# MCU.net
KiCad netlist of a schematic drawn in Altium Designer
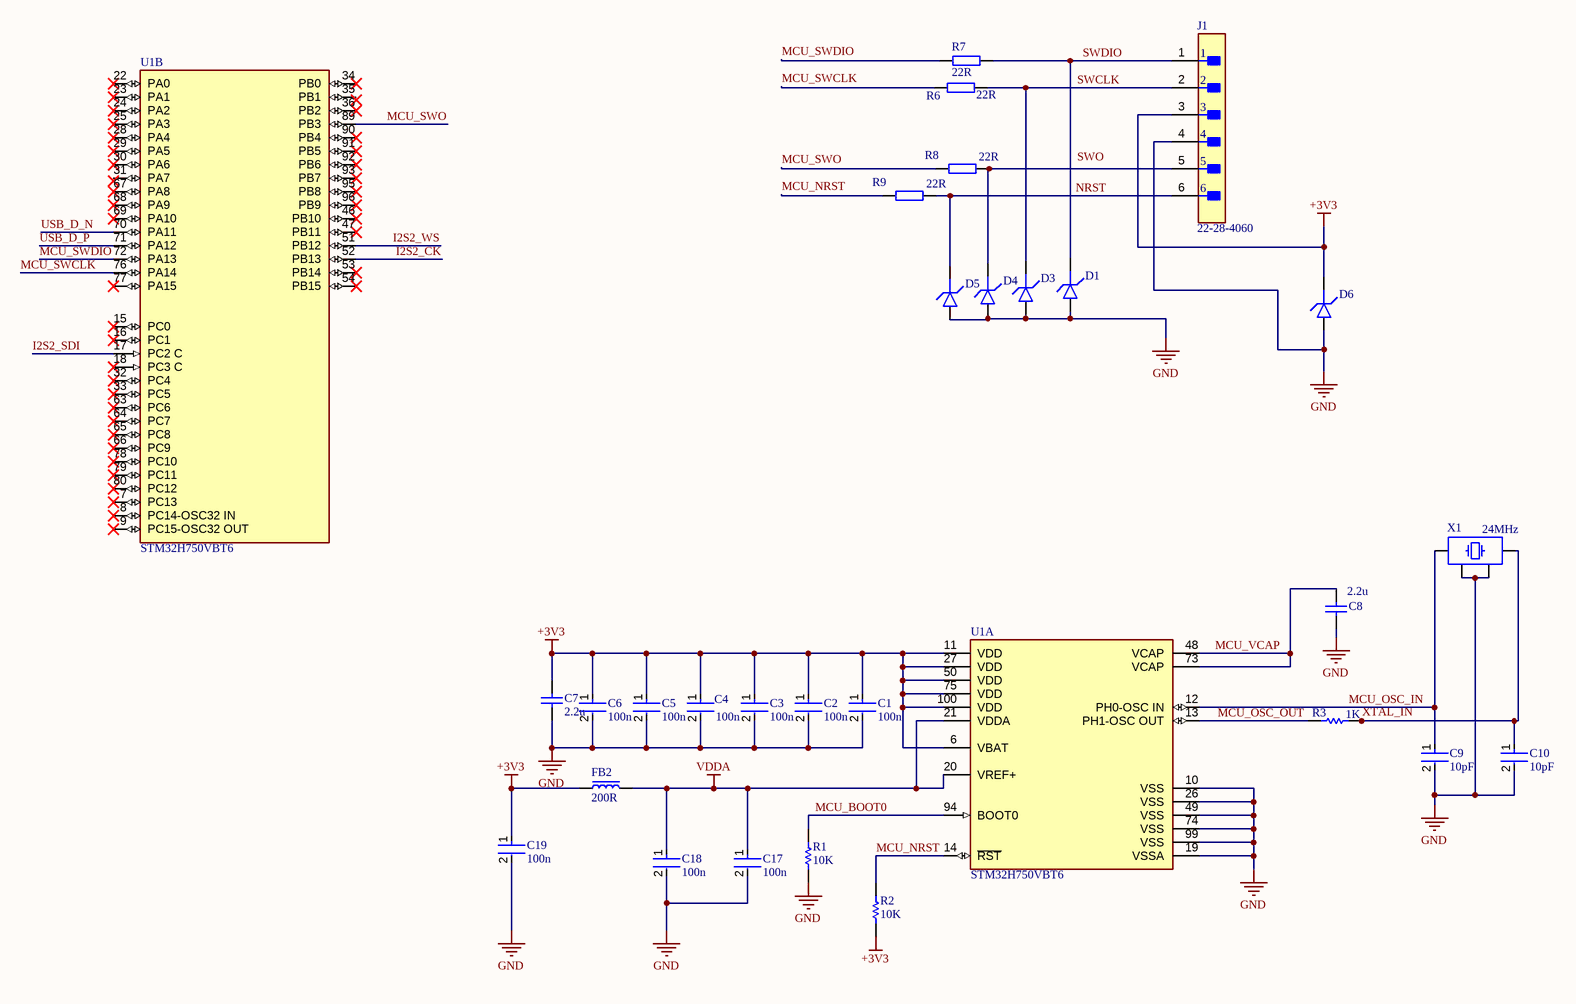
[diagram p0: MCU.SchDoc]

(export (version "E")
  (design (tool "Eeschema 10.0.6"))
  (components
    (comp (ref "C1")
      (value "100n")
      (footprint "FP-C0402-BB-MFG")
      (description "C0402 0.10 μF X7R 5.00% 16 V")
      (fields
        (field (name "OCTOPART") "https://octopart.com/c0402c104j4rac-kemet-24931384")
        (field (name "MANUFACTURER") "Kemet")
      )
      (libsource (lib "Altium Content Vault") (part "b4654b650e69147ec39a6b967a45e02"))
    )
    (comp (ref "C2")
      (value "100n")
      (footprint "FP-C0402-BB-MFG")
      (description "C0402 0.10 μF X7R 5.00% 16 V")
      (fields
        (field (name "OCTOPART") "https://octopart.com/c0402c104j4rac-kemet-24931384")
        (field (name "MANUFACTURER") "Kemet")
      )
      (libsource (lib "Altium Content Vault") (part "b4654b650e69147ec39a6b967a45e02"))
    )
    (comp (ref "C3")
      (value "100n")
      (footprint "FP-C0402-BB-MFG")
      (description "C0402 0.10 μF X7R 5.00% 16 V")
      (fields
        (field (name "OCTOPART") "https://octopart.com/c0402c104j4rac-kemet-24931384")
        (field (name "MANUFACTURER") "Kemet")
      )
      (libsource (lib "Altium Content Vault") (part "b4654b650e69147ec39a6b967a45e02"))
    )
    (comp (ref "C4")
      (value "100n")
      (footprint "FP-C0402-BB-MFG")
      (description "C0402 0.10 μF X7R 5.00% 16 V")
      (fields
        (field (name "OCTOPART") "https://octopart.com/c0402c104j4rac-kemet-24931384")
        (field (name "MANUFACTURER") "Kemet")
      )
      (libsource (lib "Altium Content Vault") (part "b4654b650e69147ec39a6b967a45e02"))
    )
    (comp (ref "C5")
      (value "100n")
      (footprint "FP-C0402-BB-MFG")
      (description "C0402 0.10 μF X7R 5.00% 16 V")
      (fields
        (field (name "OCTOPART") "https://octopart.com/c0402c104j4rac-kemet-24931384")
        (field (name "MANUFACTURER") "Kemet")
      )
      (libsource (lib "Altium Content Vault") (part "b4654b650e69147ec39a6b967a45e02"))
    )
    (comp (ref "C6")
      (value "100n")
      (footprint "FP-C0402-BB-MFG")
      (description "C0402 0.10 μF X7R 5.00% 16 V")
      (fields
        (field (name "OCTOPART") "https://octopart.com/c0402c104j4rac-kemet-24931384")
        (field (name "MANUFACTURER") "Kemet")
      )
      (libsource (lib "Altium Content Vault") (part "b4654b650e69147ec39a6b967a45e02"))
    )
    (comp (ref "C7")
      (value "2.2u")
      (footprint "CAPC1608X90X35NL15T15")
      (fields (field (name "MANUFACTURER") "Kemet") (field (name "PART NUMBER") "C0603C225M4PACTU"))
      (libsource (lib "Altium Content Vault") (part "CAP"))
    )
    (comp (ref "C8")
      (value "2.2u")
      (footprint "CAPC1608X90X35NL15T15")
      (fields (field (name "MANUFACTURER") "Kemet") (field (name "PART NUMBER") "C0603C225M4PACTU"))
      (libsource (lib "Altium Content Vault") (part "CAP"))
    )
    (comp (ref "C9")
      (value "10pF")
      (footprint "FP-C0402-BB-MFG")
      (description "CAP CER 10PF 16V NP0 0402")
      (fields
        (field (name "MANUFACTURER PART NUMBER") "C0402C100J4GACTU")
        (field (name "MANUFACTURER") "Kemet")
      )
      (libsource (lib "Altium Content Vault") (part "b4654b650e69147ec39a6b967a45e02"))
    )
    (comp (ref "C10")
      (value "10pF")
      (footprint "FP-C0402-BB-MFG")
      (description "CAP CER 10PF 16V NP0 0402")
      (fields
        (field (name "MANUFACTURER PART NUMBER") "C0402C100J4GACTU")
        (field (name "MANUFACTURER") "Kemet")
      )
      (libsource (lib "Altium Content Vault") (part "b4654b650e69147ec39a6b967a45e02"))
    )
    (comp (ref "C17")
      (value "100n")
      (footprint "FP-C0402-BB-MFG")
      (description "C0402 0.10 μF X7R 5.00% 16 V")
      (fields
        (field (name "OCTOPART") "https://octopart.com/c0402c104j4rac-kemet-24931384")
        (field (name "MANUFACTURER") "Kemet")
      )
      (libsource (lib "Altium Content Vault") (part "b4654b650e69147ec39a6b967a45e02"))
    )
    (comp (ref "C18")
      (value "100n")
      (footprint "FP-C0402-BB-MFG")
      (description "C0402 0.10 μF X7R 5.00% 16 V")
      (fields
        (field (name "OCTOPART") "https://octopart.com/c0402c104j4rac-kemet-24931384")
        (field (name "MANUFACTURER") "Kemet")
      )
      (libsource (lib "Altium Content Vault") (part "b4654b650e69147ec39a6b967a45e02"))
    )
    (comp (ref "C19")
      (value "100n")
      (footprint "FP-C0402-BB-MFG")
      (description "C0402 0.10 μF X7R 5.00% 16 V")
      (fields
        (field (name "OCTOPART") "https://octopart.com/c0402c104j4rac-kemet-24931384")
        (field (name "MANUFACTURER") "Kemet")
      )
      (libsource (lib "Altium Content Vault") (part "b4654b650e69147ec39a6b967a45e02"))
    )
    (comp (ref "D1")
      (value "~")
      (footprint "D_0402")
      (description "Diode TVS / ESD 0402")
      (libsource (lib "Schematic-Lib-PhilsLab") (part "D_TVS_0402"))
    )
    (comp (ref "D3")
      (value "~")
      (footprint "D_0402")
      (description "Diode TVS / ESD 0402")
      (libsource (lib "Schematic-Lib-PhilsLab") (part "D_TVS_0402"))
    )
    (comp (ref "D4")
      (value "~")
      (footprint "D_0402")
      (description "Diode TVS / ESD 0402")
      (libsource (lib "Schematic-Lib-PhilsLab") (part "D_TVS_0402"))
    )
    (comp (ref "D5")
      (value "~")
      (footprint "D_0402")
      (description "Diode TVS / ESD 0402")
      (libsource (lib "Schematic-Lib-PhilsLab") (part "D_TVS_0402"))
    )
    (comp (ref "D6")
      (value "~")
      (footprint "D_0402")
      (description "Diode TVS / ESD 0402")
      (libsource (lib "Schematic-Lib-PhilsLab") (part "D_TVS_0402"))
    )
    (comp (ref "FB2")
      (value "200R")
      (footprint "FB_0603")
      (description "Ferrite Bead SMD 0603")
      (libsource (lib "Schematic-Lib-PhilsLab") (part "FB_0603"))
    )
    (comp (ref "J1")
      (value "22-28-4060")
      (footprint "FP-22-28-4060-MFG")
      (description "CONN HEADER VERT 6POS 2.54MM")
      (libsource (lib "Altium Content Vault") (part "f2cb566baf1c37ab5a3b8e90bbeafd6"))
    )
    (comp (ref "R1")
      (value "10K")
      (footprint "RESC1005X40X25ML05T05")
      (fields (field (name "PART NUMBER") "ERJ-2GEJ103X") (field (name "MANUFACTURER") "Panasonic"))
      (libsource (lib "Altium Content Vault") (part "RES"))
    )
    (comp (ref "R2")
      (value "10K")
      (footprint "RESC1005X40X25ML05T05")
      (fields (field (name "PART NUMBER") "ERJ-2GEJ103X") (field (name "MANUFACTURER") "Panasonic"))
      (libsource (lib "Altium Content Vault") (part "RES"))
    )
    (comp (ref "R3")
      (value "1K")
      (footprint "RESC1005X40X25NL05T05")
      (fields (field (name "MANUFACTURER") "Panasonic") (field (name "PART NUMBER") "ERJ-2GEJ102X"))
      (libsource (lib "Altium Content Vault") (part "RES"))
    )
    (comp (ref "R6")
      (value "22R")
      (footprint "RES_0402")
      (description "Resistor SMD 0402")
      (libsource (lib "Schematic-Lib-PhilsLab") (part "RES_0402"))
    )
    (comp (ref "R7")
      (value "22R")
      (footprint "RES_0402")
      (description "Resistor SMD 0402")
      (libsource (lib "Schematic-Lib-PhilsLab") (part "RES_0402"))
    )
    (comp (ref "R8")
      (value "22R")
      (footprint "RES_0402")
      (description "Resistor SMD 0402")
      (libsource (lib "Schematic-Lib-PhilsLab") (part "RES_0402"))
    )
    (comp (ref "R9")
      (value "22R")
      (footprint "RES_0402")
      (description "Resistor SMD 0402")
      (libsource (lib "Schematic-Lib-PhilsLab") (part "RES_0402"))
    )
    (comp (ref "U1")
      (value "STM32H750VBT6")
      (footprint "FP-LQFP100-1L-MFG")
      (description "IC MCU 32BIT 128KB FLASH 100LQFP")
      (fields
        (field (name "OCTOPART") "https://octopart.com/stm32h750vbt6-stmicroelectronics-94048547")
        (field (name "MANUFACTURER") "STMicroelectronics")
      )
      (libsource (lib "Altium Content Vault") (part "aca449acb2b80670ba40d015d68dc7a"))
    )
    (comp (ref "X1")
      (value "24MHz")
      (footprint "XTAL_3225")
      (description "Crystal SMD 24MHz 10PPM 7pF 3225")
      (fields
        (field (name "MANUFACTURER") "Epson")
        (field (name "MANUFACTURER PART NUMBER") "TSX-3225 24.0000MF15X-AC")
      )
      (libsource (lib "Schematic-Lib-PhilsLab") (part "TSX-3225_24.0000MF15X-AC"))
    )
  )
  (nets
    (net (code "1") (name "+3V3") (class "Default")
      (node (ref "C1") (pin "1") (pinfunction "1_1") (pintype "passive"))
      (node (ref "C19") (pin "1") (pinfunction "1_1") (pintype "passive"))
      (node (ref "C2") (pin "1") (pinfunction "1_1") (pintype "passive"))
      (node (ref "C3") (pin "1") (pinfunction "1_1") (pintype "passive"))
      (node (ref "C4") (pin "1") (pinfunction "1_1") (pintype "passive"))
      (node (ref "C5") (pin "1") (pinfunction "1_1") (pintype "passive"))
      (node (ref "C6") (pin "1") (pinfunction "1_1") (pintype "passive"))
      (node (ref "C7") (pin "2") (pinfunction "2_2") (pintype "passive"))
      (node (ref "D6") (pin "K") (pinfunction "K_K") (pintype "passive"))
      (node (ref "FB2") (pin "1") (pinfunction "1_1") (pintype "passive"))
      (node (ref "J1") (pin "3") (pinfunction "3_3") (pintype "passive"))
      (node (ref "R2") (pin "1") (pinfunction "1_1") (pintype "passive"))
      (node (ref "U1") (pin "100") (pinfunction "VDD_100") (pintype "power_in"))
      (node (ref "U1") (pin "11") (pinfunction "VDD_11") (pintype "power_in"))
      (node (ref "U1") (pin "27") (pinfunction "VDD_27") (pintype "power_in"))
      (node (ref "U1") (pin "50") (pinfunction "VDD_50") (pintype "power_in"))
      (node (ref "U1") (pin "6") (pinfunction "VBAT_6") (pintype "power_in"))
      (node (ref "U1") (pin "75") (pinfunction "VDD_75") (pintype "power_in"))
    )
    (net (code "2") (name "/I2S2_CK") (class "Default")
      (node (ref "U1") (pin "52") (pinfunction "PB13_52") (pintype "bidirectional"))
    )
    (net (code "3") (name "/I2S2_SDI") (class "Default")
      (node (ref "U1") (pin "17") (pinfunction "PC2_C_17") (pintype "input"))
    )
    (net (code "4") (name "/I2S2_WS") (class "Default")
      (node (ref "U1") (pin "51") (pinfunction "PB12_51") (pintype "bidirectional"))
    )
    (net (code "5") (name "/MCU_BOOT0") (class "Default")
      (node (ref "R1") (pin "2") (pinfunction "2_2") (pintype "passive"))
      (node (ref "U1") (pin "94") (pinfunction "BOOT0_94") (pintype "input"))
    )
    (net (code "6") (name "/MCU_NRST") (class "Default")
      (node (ref "R2") (pin "2") (pinfunction "2_2") (pintype "passive"))
      (node (ref "R9") (pin "1") (pinfunction "1_1") (pintype "passive"))
      (node (ref "U1") (pin "14") (pinfunction "~{RST}_14") (pintype "bidirectional"))
    )
    (net (code "7") (name "/MCU_OSC_IN") (class "Default")
      (node (ref "C9") (pin "1") (pinfunction "1_1") (pintype "passive"))
      (node (ref "U1") (pin "12") (pinfunction "PH0-OSC_IN_12") (pintype "bidirectional"))
      (node (ref "X1") (pin "1") (pinfunction "1_1") (pintype "passive"))
    )
    (net (code "8") (name "/MCU_OSC_OUT") (class "Default")
      (node (ref "R3") (pin "1") (pinfunction "1_1") (pintype "passive"))
      (node (ref "U1") (pin "13") (pinfunction "PH1-OSC_OUT_13") (pintype "bidirectional"))
    )
    (net (code "9") (name "/MCU_SWCLK") (class "Default")
      (node (ref "R6") (pin "1") (pinfunction "1_1") (pintype "passive"))
      (node (ref "U1") (pin "76") (pinfunction "PA14_76") (pintype "bidirectional"))
    )
    (net (code "10") (name "/MCU_SWDIO") (class "Default")
      (node (ref "R7") (pin "1") (pinfunction "1_1") (pintype "passive"))
      (node (ref "U1") (pin "72") (pinfunction "PA13_72") (pintype "bidirectional"))
    )
    (net (code "11") (name "/MCU_SWO") (class "Default")
      (node (ref "R8") (pin "1") (pinfunction "1_1") (pintype "passive"))
      (node (ref "U1") (pin "89") (pinfunction "PB3_89") (pintype "bidirectional"))
    )
    (net (code "12") (name "/MCU_VCAP") (class "Default")
      (node (ref "C8") (pin "1") (pinfunction "1_1") (pintype "passive"))
      (node (ref "U1") (pin "48") (pinfunction "VCAP_48") (pintype "power_in"))
      (node (ref "U1") (pin "73") (pinfunction "VCAP_73") (pintype "power_in"))
    )
    (net (code "13") (name "/NRST") (class "Default")
      (node (ref "D5") (pin "K") (pinfunction "K_K") (pintype "passive"))
      (node (ref "J1") (pin "6") (pinfunction "6_6") (pintype "passive"))
      (node (ref "R9") (pin "2") (pinfunction "2_2") (pintype "passive"))
    )
    (net (code "14") (name "/SWCLK") (class "Default")
      (node (ref "D3") (pin "K") (pinfunction "K_K") (pintype "passive"))
      (node (ref "J1") (pin "2") (pinfunction "2_2") (pintype "passive"))
      (node (ref "R6") (pin "2") (pinfunction "2_2") (pintype "passive"))
    )
    (net (code "15") (name "/SWDIO") (class "Default")
      (node (ref "D1") (pin "K") (pinfunction "K_K") (pintype "passive"))
      (node (ref "J1") (pin "1") (pinfunction "1_1") (pintype "passive"))
      (node (ref "R7") (pin "2") (pinfunction "2_2") (pintype "passive"))
    )
    (net (code "17") (name "/USB_D_N") (class "Default")
      (node (ref "U1") (pin "70") (pinfunction "PA11_70") (pintype "bidirectional"))
    )
    (net (code "18") (name "/USB_D_P") (class "Default")
      (node (ref "U1") (pin "71") (pinfunction "PA12_71") (pintype "bidirectional"))
    )
    (net (code "19") (name "/XTAL_IN") (class "Default")
      (node (ref "C10") (pin "1") (pinfunction "1_1") (pintype "passive"))
      (node (ref "R3") (pin "2") (pinfunction "2_2") (pintype "passive"))
      (node (ref "X1") (pin "3") (pinfunction "3_3") (pintype "passive"))
    )
    (net (code "20") (name "GND") (class "Default")
      (node (ref "C1") (pin "2") (pinfunction "2_2") (pintype "passive"))
      (node (ref "C10") (pin "2") (pinfunction "2_2") (pintype "passive"))
      (node (ref "C17") (pin "2") (pinfunction "2_2") (pintype "passive"))
      (node (ref "C18") (pin "2") (pinfunction "2_2") (pintype "passive"))
      (node (ref "C19") (pin "2") (pinfunction "2_2") (pintype "passive"))
      (node (ref "C2") (pin "2") (pinfunction "2_2") (pintype "passive"))
      (node (ref "C3") (pin "2") (pinfunction "2_2") (pintype "passive"))
      (node (ref "C4") (pin "2") (pinfunction "2_2") (pintype "passive"))
      (node (ref "C5") (pin "2") (pinfunction "2_2") (pintype "passive"))
      (node (ref "C6") (pin "2") (pinfunction "2_2") (pintype "passive"))
      (node (ref "C7") (pin "1") (pinfunction "1_1") (pintype "passive"))
      (node (ref "C8") (pin "2") (pinfunction "2_2") (pintype "passive"))
      (node (ref "C9") (pin "2") (pinfunction "2_2") (pintype "passive"))
      (node (ref "D1") (pin "A") (pinfunction "A_A") (pintype "passive"))
      (node (ref "D3") (pin "A") (pinfunction "A_A") (pintype "passive"))
      (node (ref "D4") (pin "A") (pinfunction "A_A") (pintype "passive"))
      (node (ref "D5") (pin "A") (pinfunction "A_A") (pintype "passive"))
      (node (ref "D6") (pin "A") (pinfunction "A_A") (pintype "passive"))
      (node (ref "J1") (pin "4") (pinfunction "4_4") (pintype "passive"))
      (node (ref "R1") (pin "1") (pinfunction "1_1") (pintype "passive"))
      (node (ref "U1") (pin "10") (pinfunction "VSS_10") (pintype "power_in"))
      (node (ref "U1") (pin "19") (pinfunction "VSSA_19") (pintype "power_in"))
      (node (ref "U1") (pin "26") (pinfunction "VSS_26") (pintype "power_in"))
      (node (ref "U1") (pin "49") (pinfunction "VSS_49") (pintype "power_in"))
      (node (ref "U1") (pin "74") (pinfunction "VSS_74") (pintype "power_in"))
      (node (ref "U1") (pin "99") (pinfunction "VSS_99") (pintype "power_in"))
      (node (ref "X1") (pin "2") (pinfunction "2_2") (pintype "passive"))
      (node (ref "X1") (pin "4") (pinfunction "4_4") (pintype "passive"))
    )
    (net (code "21") (name "Net-(D4-PadK)") (class "Default")
      (node (ref "D4") (pin "K") (pinfunction "K_K") (pintype "passive"))
      (node (ref "J1") (pin "5") (pinfunction "5_5") (pintype "passive"))
      (node (ref "R8") (pin "2") (pinfunction "2_2") (pintype "passive"))
    )
    (net (code "22") (name "VDDA") (class "Default")
      (node (ref "C17") (pin "1") (pinfunction "1_1") (pintype "passive"))
      (node (ref "C18") (pin "1") (pinfunction "1_1") (pintype "passive"))
      (node (ref "FB2") (pin "2") (pinfunction "2_2") (pintype "passive"))
      (node (ref "U1") (pin "20") (pinfunction "VREF+_20") (pintype "power_in"))
      (node (ref "U1") (pin "21") (pinfunction "VDDA_21") (pintype "power_in"))
    )
    (net (code "23") (name "unconnected-(U1B-PA0-Pad22)") (class "Default")
      (node (ref "U1") (pin "22") (pinfunction "PA0_22") (pintype "bidirectional+no_connect"))
    )
    (net (code "24") (name "unconnected-(U1B-PA1-Pad23)") (class "Default")
      (node (ref "U1") (pin "23") (pinfunction "PA1_23") (pintype "bidirectional+no_connect"))
    )
    (net (code "25") (name "unconnected-(U1B-PA2-Pad24)") (class "Default")
      (node (ref "U1") (pin "24") (pinfunction "PA2_24") (pintype "bidirectional+no_connect"))
    )
    (net (code "26") (name "unconnected-(U1B-PA3-Pad25)") (class "Default")
      (node (ref "U1") (pin "25") (pinfunction "PA3_25") (pintype "bidirectional+no_connect"))
    )
    (net (code "27") (name "unconnected-(U1B-PA4-Pad28)") (class "Default")
      (node (ref "U1") (pin "28") (pinfunction "PA4_28") (pintype "bidirectional+no_connect"))
    )
    (net (code "28") (name "unconnected-(U1B-PA5-Pad29)") (class "Default")
      (node (ref "U1") (pin "29") (pinfunction "PA5_29") (pintype "bidirectional+no_connect"))
    )
    (net (code "29") (name "unconnected-(U1B-PA6-Pad30)") (class "Default")
      (node (ref "U1") (pin "30") (pinfunction "PA6_30") (pintype "bidirectional+no_connect"))
    )
    (net (code "30") (name "unconnected-(U1B-PA7-Pad31)") (class "Default")
      (node (ref "U1") (pin "31") (pinfunction "PA7_31") (pintype "bidirectional"))
    )
    (net (code "31") (name "unconnected-(U1B-PA8-Pad67)") (class "Default")
      (node (ref "U1") (pin "67") (pinfunction "PA8_67") (pintype "bidirectional+no_connect"))
    )
    (net (code "32") (name "unconnected-(U1B-PA9-Pad68)") (class "Default")
      (node (ref "U1") (pin "68") (pinfunction "PA9_68") (pintype "bidirectional+no_connect"))
    )
    (net (code "33") (name "unconnected-(U1B-PA10-Pad69)") (class "Default")
      (node (ref "U1") (pin "69") (pinfunction "PA10_69") (pintype "bidirectional+no_connect"))
    )
    (net (code "34") (name "unconnected-(U1B-PA15-Pad77)") (class "Default")
      (node (ref "U1") (pin "77") (pinfunction "PA15_77") (pintype "bidirectional+no_connect"))
    )
    (net (code "35") (name "unconnected-(U1B-PB0-Pad34)") (class "Default")
      (node (ref "U1") (pin "34") (pinfunction "PB0_34") (pintype "bidirectional+no_connect"))
    )
    (net (code "36") (name "unconnected-(U1B-PB1-Pad35)") (class "Default")
      (node (ref "U1") (pin "35") (pinfunction "PB1_35") (pintype "bidirectional"))
    )
    (net (code "37") (name "unconnected-(U1B-PB2-Pad36)") (class "Default")
      (node (ref "U1") (pin "36") (pinfunction "PB2_36") (pintype "bidirectional+no_connect"))
    )
    (net (code "38") (name "unconnected-(U1B-PB4-Pad90)") (class "Default")
      (node (ref "U1") (pin "90") (pinfunction "PB4_90") (pintype "bidirectional+no_connect"))
    )
    (net (code "39") (name "unconnected-(U1B-PB5-Pad91)") (class "Default")
      (node (ref "U1") (pin "91") (pinfunction "PB5_91") (pintype "bidirectional+no_connect"))
    )
    (net (code "40") (name "unconnected-(U1B-PB6-Pad92)") (class "Default")
      (node (ref "U1") (pin "92") (pinfunction "PB6_92") (pintype "bidirectional+no_connect"))
    )
    (net (code "41") (name "unconnected-(U1B-PB7-Pad93)") (class "Default")
      (node (ref "U1") (pin "93") (pinfunction "PB7_93") (pintype "bidirectional+no_connect"))
    )
    (net (code "42") (name "unconnected-(U1B-PB8-Pad95)") (class "Default")
      (node (ref "U1") (pin "95") (pinfunction "PB8_95") (pintype "bidirectional+no_connect"))
    )
    (net (code "43") (name "unconnected-(U1B-PB9-Pad96)") (class "Default")
      (node (ref "U1") (pin "96") (pinfunction "PB9_96") (pintype "bidirectional+no_connect"))
    )
    (net (code "44") (name "unconnected-(U1B-PB10-Pad46)") (class "Default")
      (node (ref "U1") (pin "46") (pinfunction "PB10_46") (pintype "bidirectional+no_connect"))
    )
    (net (code "45") (name "unconnected-(U1B-PB11-Pad47)") (class "Default")
      (node (ref "U1") (pin "47") (pinfunction "PB11_47") (pintype "bidirectional+no_connect"))
    )
    (net (code "46") (name "unconnected-(U1B-PB14-Pad53)") (class "Default")
      (node (ref "U1") (pin "53") (pinfunction "PB14_53") (pintype "bidirectional+no_connect"))
    )
    (net (code "47") (name "unconnected-(U1B-PB15-Pad54)") (class "Default")
      (node (ref "U1") (pin "54") (pinfunction "PB15_54") (pintype "bidirectional+no_connect"))
    )
    (net (code "48") (name "unconnected-(U1B-PC0-Pad15)") (class "Default")
      (node (ref "U1") (pin "15") (pinfunction "PC0_15") (pintype "bidirectional+no_connect"))
    )
    (net (code "49") (name "unconnected-(U1B-PC1-Pad16)") (class "Default")
      (node (ref "U1") (pin "16") (pinfunction "PC1_16") (pintype "bidirectional+no_connect"))
    )
    (net (code "50") (name "unconnected-(U1B-PC3_C-Pad18)") (class "Default")
      (node (ref "U1") (pin "18") (pinfunction "PC3_C_18") (pintype "input+no_connect"))
    )
    (net (code "51") (name "unconnected-(U1B-PC4-Pad32)") (class "Default")
      (node (ref "U1") (pin "32") (pinfunction "PC4_32") (pintype "bidirectional+no_connect"))
    )
    (net (code "52") (name "unconnected-(U1B-PC5-Pad33)") (class "Default")
      (node (ref "U1") (pin "33") (pinfunction "PC5_33") (pintype "bidirectional+no_connect"))
    )
    (net (code "53") (name "unconnected-(U1B-PC6-Pad63)") (class "Default")
      (node (ref "U1") (pin "63") (pinfunction "PC6_63") (pintype "bidirectional+no_connect"))
    )
    (net (code "54") (name "unconnected-(U1B-PC7-Pad64)") (class "Default")
      (node (ref "U1") (pin "64") (pinfunction "PC7_64") (pintype "bidirectional+no_connect"))
    )
    (net (code "55") (name "unconnected-(U1B-PC8-Pad65)") (class "Default")
      (node (ref "U1") (pin "65") (pinfunction "PC8_65") (pintype "bidirectional+no_connect"))
    )
    (net (code "56") (name "unconnected-(U1B-PC9-Pad66)") (class "Default")
      (node (ref "U1") (pin "66") (pinfunction "PC9_66") (pintype "bidirectional+no_connect"))
    )
    (net (code "57") (name "unconnected-(U1B-PC10-Pad78)") (class "Default")
      (node (ref "U1") (pin "78") (pinfunction "PC10_78") (pintype "bidirectional+no_connect"))
    )
    (net (code "58") (name "unconnected-(U1B-PC11-Pad79)") (class "Default")
      (node (ref "U1") (pin "79") (pinfunction "PC11_79") (pintype "bidirectional+no_connect"))
    )
    (net (code "59") (name "unconnected-(U1B-PC12-Pad80)") (class "Default")
      (node (ref "U1") (pin "80") (pinfunction "PC12_80") (pintype "bidirectional+no_connect"))
    )
    (net (code "60") (name "unconnected-(U1B-PC13-Pad7)") (class "Default")
      (node (ref "U1") (pin "7") (pinfunction "PC13_7") (pintype "bidirectional+no_connect"))
    )
    (net (code "61") (name "unconnected-(U1B-PC14-OSC32_IN-Pad8)") (class "Default")
      (node (ref "U1") (pin "8") (pinfunction "PC14-OSC32_IN_8") (pintype "bidirectional+no_connect"))
    )
    (net (code "62") (name "unconnected-(U1B-PC15-OSC32_OUT-Pad9)") (class "Default")
      (node (ref "U1") (pin "9") (pinfunction "PC15-OSC32_OUT_9") (pintype "bidirectional+no_connect"))
    )
  )
)
